# timer_power.net
KiCad netlist of a schematic drawn in Altium Designer
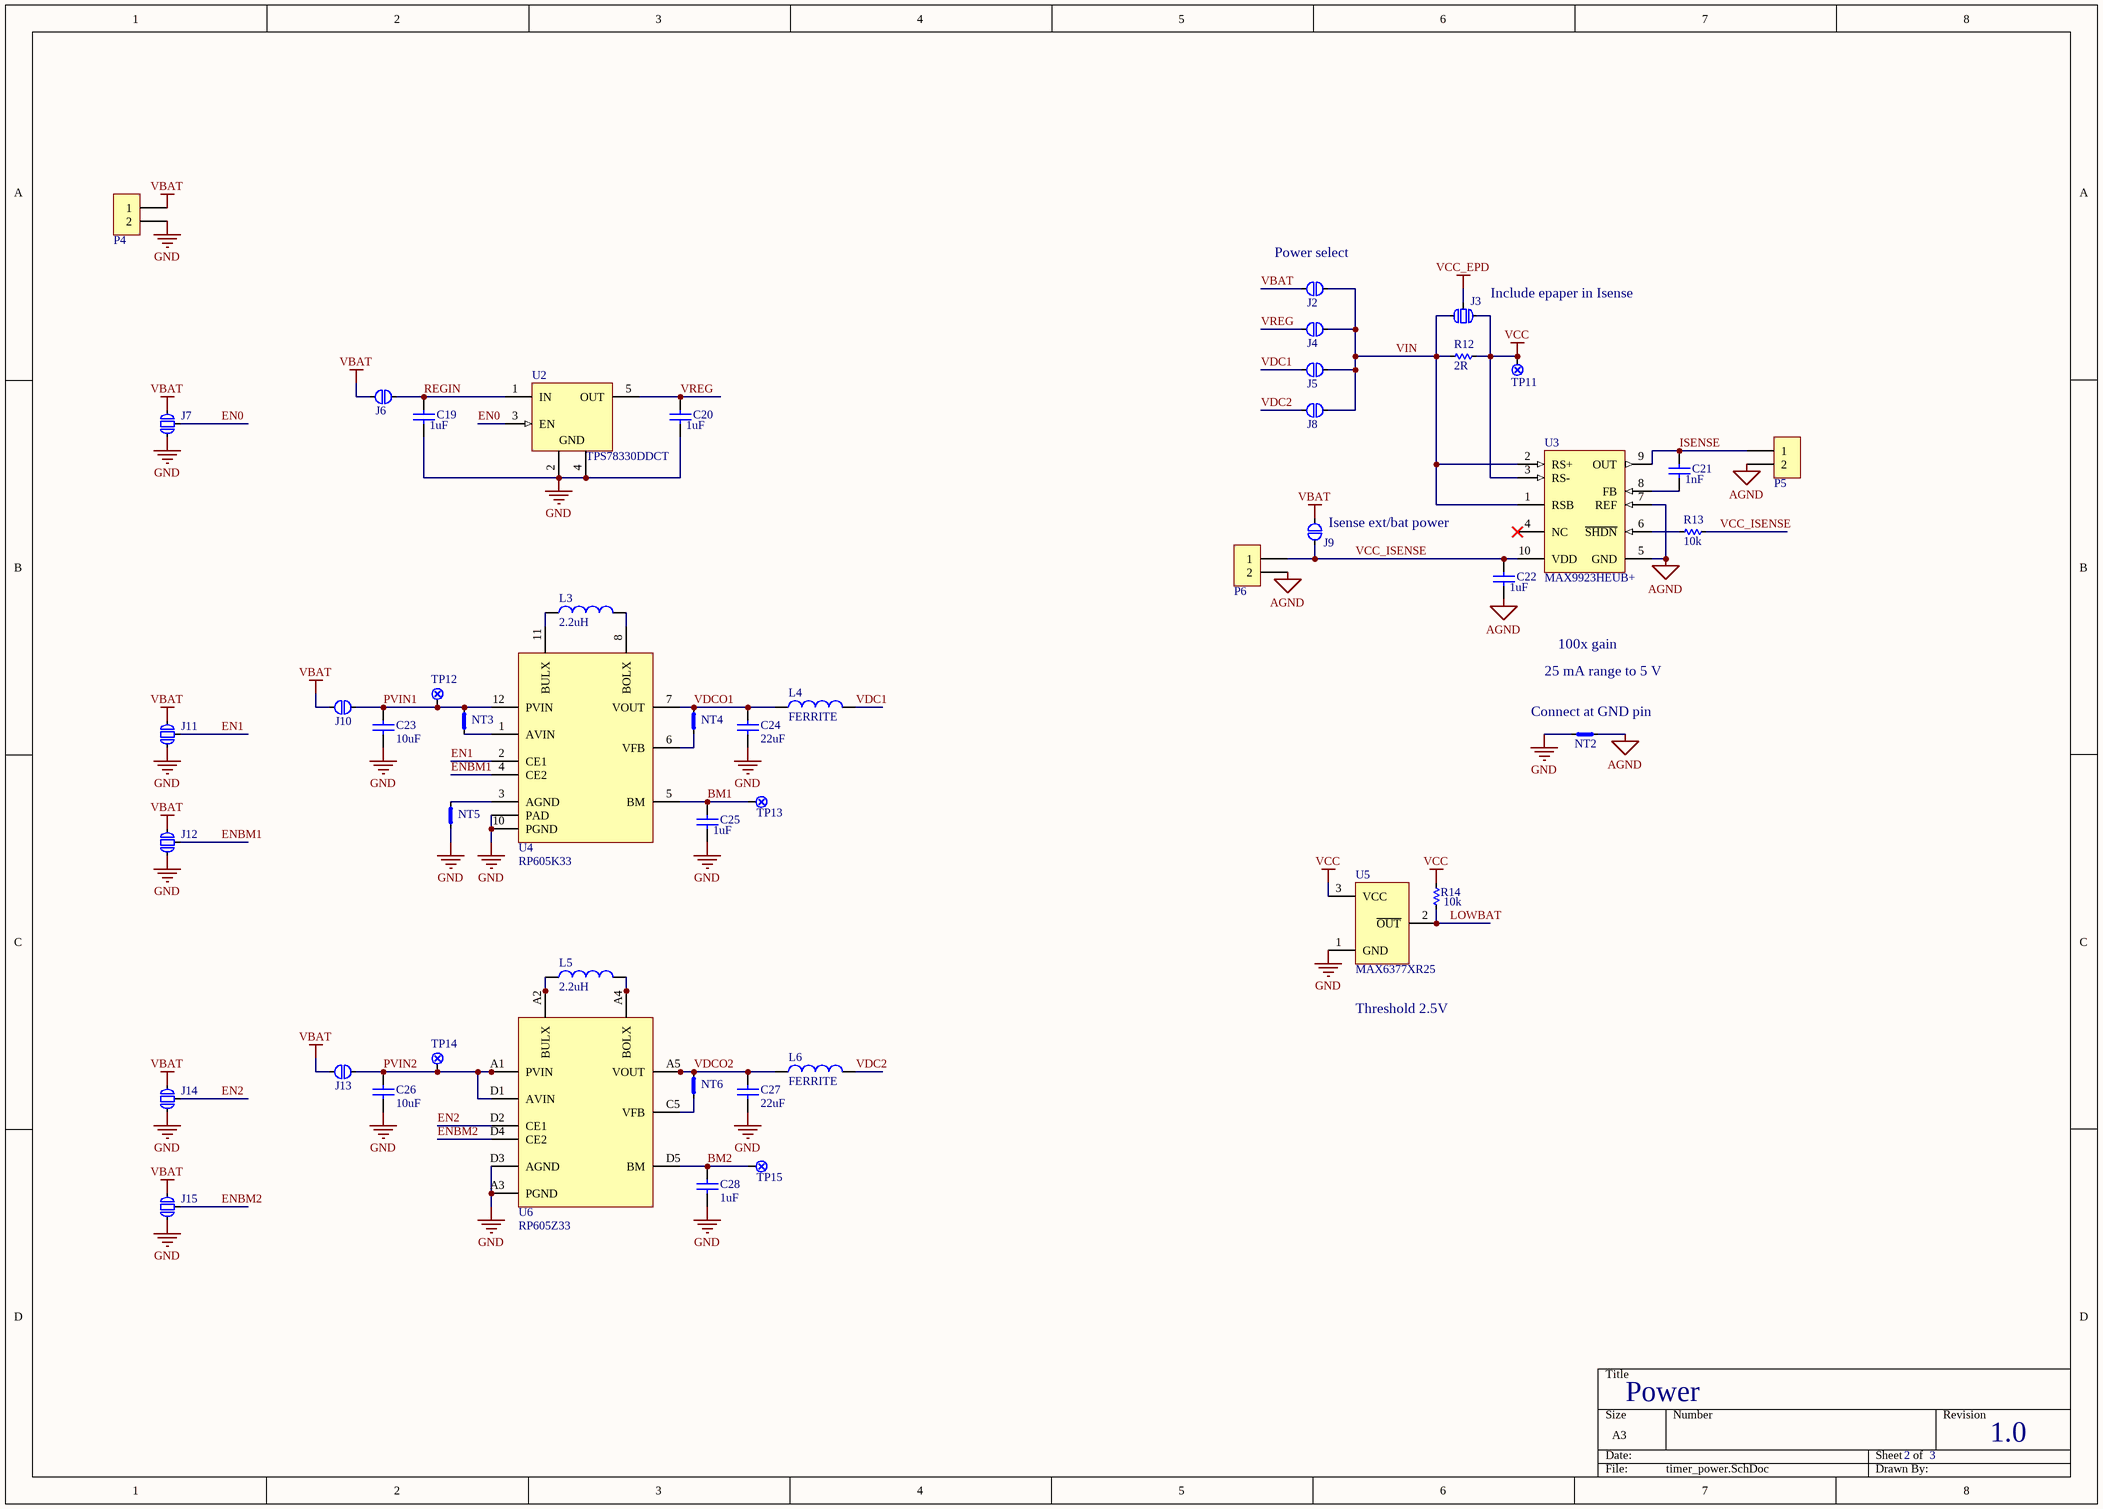
[diagram p0: timer_power.SchDoc]

(export (version "E")
  (design (tool "Eeschema 10.0.6"))
  (components
    (comp (ref "C19")
      (value "1uF")
      (footprint "C0603/1608")
      (description "Capacitor")
      (fields (field (name "TOLERANCE") "x%") (field (name "VOLTAGE") "6.3V"))
      (libsource (lib "ZMPlib") (part "CAP"))
    )
    (comp (ref "C20")
      (value "1uF")
      (footprint "C0603/1608")
      (description "Capacitor")
      (fields (field (name "TOLERANCE") "x%") (field (name "VOLTAGE") "6.3V"))
      (libsource (lib "ZMPlib") (part "CAP"))
    )
    (comp (ref "C21")
      (value "1nF")
      (footprint "C0603/1608")
      (description "Capacitor")
      (fields (field (name "TOLERANCE") "x%") (field (name "VOLTAGE") "6.3V"))
      (libsource (lib "ZMPlib") (part "CAP"))
    )
    (comp (ref "C22")
      (value "1uF")
      (footprint "C0603/1608")
      (description "Capacitor")
      (fields (field (name "TOLERANCE") "x%") (field (name "VOLTAGE") "6.3V"))
      (libsource (lib "ZMPlib") (part "CAP"))
    )
    (comp (ref "C23")
      (value "10uF")
      (footprint "C0805/2012")
      (description "Capacitor")
      (fields (field (name "TOLERANCE") "x%") (field (name "VOLTAGE") "6.3V"))
      (libsource (lib "ZMPlib") (part "CAP"))
    )
    (comp (ref "C24")
      (value "22uF")
      (footprint "C0805/2012")
      (description "Capacitor")
      (fields (field (name "TOLERANCE") "x%") (field (name "VOLTAGE") "6.3V"))
      (libsource (lib "ZMPlib") (part "CAP"))
    )
    (comp (ref "C25")
      (value "1uF")
      (footprint "C0603/1608")
      (description "Capacitor")
      (fields (field (name "TOLERANCE") "x%") (field (name "VOLTAGE") "6.3V"))
      (libsource (lib "ZMPlib") (part "CAP"))
    )
    (comp (ref "C26")
      (value "10uF")
      (footprint "C0805/2012")
      (description "Capacitor")
      (fields (field (name "TOLERANCE") "x%") (field (name "VOLTAGE") "6.3V"))
      (libsource (lib "ZMPlib") (part "CAP"))
    )
    (comp (ref "C27")
      (value "22uF")
      (footprint "C0805/2012")
      (description "Capacitor")
      (fields (field (name "TOLERANCE") "x%") (field (name "VOLTAGE") "6.3V"))
      (libsource (lib "ZMPlib") (part "CAP"))
    )
    (comp (ref "C28")
      (value "1uF")
      (footprint "C0603/1608")
      (description "Capacitor")
      (fields (field (name "TOLERANCE") "x%") (field (name "VOLTAGE") "6.3V"))
      (libsource (lib "ZMPlib") (part "CAP"))
    )
    (comp (ref "J2")
      (value "SEL2")
      (footprint "JMP2")
      (description "solderable jumper")
      (libsource (lib "ZMPlib") (part "SEL2"))
    )
    (comp (ref "J3")
      (value "SEL3")
      (footprint "JMP3")
      (description "solderable jumper")
      (libsource (lib "") (part "SEL3_1"))
    )
    (comp (ref "J4")
      (value "SEL2")
      (footprint "JMP2")
      (description "solderable jumper")
      (libsource (lib "ZMPlib") (part "SEL2"))
    )
    (comp (ref "J5")
      (value "SEL2")
      (footprint "JMP2")
      (description "solderable jumper")
      (libsource (lib "ZMPlib") (part "SEL2"))
    )
    (comp (ref "J6")
      (value "SEL2")
      (footprint "JMP2")
      (description "solderable jumper")
      (libsource (lib "ZMPlib") (part "SEL2"))
    )
    (comp (ref "J7")
      (value "SEL3")
      (footprint "JMP3")
      (description "solderable jumper")
      (libsource (lib "ZMPlib") (part "SEL3"))
    )
    (comp (ref "J8")
      (value "SEL2")
      (footprint "JMP2")
      (description "solderable jumper")
      (libsource (lib "ZMPlib") (part "SEL2"))
    )
    (comp (ref "J9")
      (value "SEL2")
      (footprint "JMP2")
      (description "solderable jumper")
      (libsource (lib "ZMPlib") (part "SEL2"))
    )
    (comp (ref "J10")
      (value "SEL2")
      (footprint "JMP2")
      (description "solderable jumper")
      (libsource (lib "ZMPlib") (part "SEL2"))
    )
    (comp (ref "J11")
      (value "SEL3")
      (footprint "JMP3")
      (description "solderable jumper")
      (libsource (lib "ZMPlib") (part "SEL3"))
    )
    (comp (ref "J12")
      (value "SEL3")
      (footprint "JMP3")
      (description "solderable jumper")
      (libsource (lib "ZMPlib") (part "SEL3"))
    )
    (comp (ref "J13")
      (value "SEL2")
      (footprint "JMP2")
      (description "solderable jumper")
      (libsource (lib "ZMPlib") (part "SEL2"))
    )
    (comp (ref "J14")
      (value "SEL3")
      (footprint "JMP3")
      (description "solderable jumper")
      (libsource (lib "ZMPlib") (part "SEL3"))
    )
    (comp (ref "J15")
      (value "SEL3")
      (footprint "JMP3")
      (description "solderable jumper")
      (libsource (lib "ZMPlib") (part "SEL3"))
    )
    (comp (ref "L3")
      (value "2.2uH")
      (footprint "IND3x3mm")
      (description "Inductor")
      (fields (field (name "Comment") "IND"))
      (libsource (lib "ZMPlib") (part "IND"))
    )
    (comp (ref "L4")
      (value "FERRITE")
      (footprint "R0603/1608")
      (description "Inductor")
      (fields (field (name "Comment") "IND"))
      (libsource (lib "ZMPlib") (part "IND"))
    )
    (comp (ref "L5")
      (value "2.2uH")
      (footprint "IND3x3mm")
      (description "Inductor")
      (fields (field (name "Comment") "IND"))
      (libsource (lib "ZMPlib") (part "IND"))
    )
    (comp (ref "L6")
      (value "FERRITE")
      (footprint "R0603/1608")
      (description "Inductor")
      (fields (field (name "Comment") "IND"))
      (libsource (lib "ZMPlib") (part "IND"))
    )
    (comp (ref "NT2")
      (value "NET_TIE")
      (footprint "NT2_0.5mm")
      (description "Link between nets")
      (libsource (lib "ZMPlib") (part "NET_TIE2"))
    )
    (comp (ref "NT3")
      (value "NET_TIE")
      (footprint "NT2_0.5mm")
      (description "Link between nets")
      (libsource (lib "ZMPlib") (part "NET_TIE2"))
    )
    (comp (ref "NT4")
      (value "NET_TIE")
      (footprint "NT2_0.5mm")
      (description "Link between nets")
      (libsource (lib "ZMPlib") (part "NET_TIE2"))
    )
    (comp (ref "NT5")
      (value "NET_TIE")
      (footprint "NT2_0.5mm")
      (description "Link between nets")
      (libsource (lib "ZMPlib") (part "NET_TIE2"))
    )
    (comp (ref "NT6")
      (value "NET_TIE")
      (footprint "NT2_0.5mm")
      (description "Link between nets")
      (libsource (lib "ZMPlib") (part "NET_TIE2"))
    )
    (comp (ref "P4")
      (value "SIL2")
      (footprint "PINS-2")
      (description "SIL package, 2 pins")
      (libsource (lib "ZMPlib") (part "SIL2"))
    )
    (comp (ref "P5")
      (value "SIL2")
      (footprint "PINS-2")
      (description "SIL package, 2 pins")
      (libsource (lib "") (part "SIL2_1"))
    )
    (comp (ref "P6")
      (value "SIL2")
      (footprint "PINS-2")
      (description "SIL package, 2 pins")
      (libsource (lib "ZMPlib") (part "SIL2"))
    )
    (comp (ref "R12")
      (value "2R")
      (footprint "R0805/2012")
      (description "Resistor")
      (fields (field (name "TOLERANCE") "x%") (field (name "Comment") "RES"))
      (libsource (lib "ZMPlib") (part "RES"))
    )
    (comp (ref "R13")
      (value "10k")
      (footprint "R0603/1608")
      (description "Resistor")
      (fields (field (name "TOLERANCE") "x%") (field (name "Comment") "RES"))
      (libsource (lib "ZMPlib") (part "RES"))
    )
    (comp (ref "R14")
      (value "10k")
      (footprint "R0603/1608")
      (description "Resistor")
      (fields (field (name "TOLERANCE") "x%") (field (name "Comment") "RES"))
      (libsource (lib "ZMPlib") (part "RES"))
    )
    (comp (ref "TP11")
      (value "TP")
      (footprint "TP-1.0")
      (description "Test point")
      (libsource (lib "ZMPlib") (part "TP"))
    )
    (comp (ref "TP12")
      (value "TP")
      (footprint "TP-1.0")
      (description "Test point")
      (libsource (lib "ZMPlib") (part "TP"))
    )
    (comp (ref "TP13")
      (value "TP")
      (footprint "TP-1.0")
      (description "Test point")
      (libsource (lib "ZMPlib") (part "TP"))
    )
    (comp (ref "TP14")
      (value "TP")
      (footprint "TP-1.0")
      (description "Test point")
      (libsource (lib "ZMPlib") (part "TP"))
    )
    (comp (ref "TP15")
      (value "TP")
      (footprint "TP-1.0")
      (description "Test point")
      (libsource (lib "ZMPlib") (part "TP"))
    )
    (comp (ref "U2")
      (value "TPS78330DDCT")
      (footprint "DDC0005A_L")
      (fields (field (name "MANUFACTURER") "Texas Instruments"))
      (libsource (lib "Altium Content Vault") (part "TI-TPS78XXX-DDC5"))
    )
    (comp (ref "U3")
      (value "MAX9923HEUB+")
      (footprint "MAXM-U10+2_N")
      (libsource (lib "Altium Content Vault") (part "MAX992X-U10+2"))
    )
    (comp (ref "U4")
      (value "RP605K33")
      (footprint "DFN(PLP)2730-12")
      (description "300mA Ultra-low Power Buck Boost DC/DC Converter with Battery Monitor, DFN-12 package")
      (libsource (lib "ZMPlib") (part "RP605xK"))
    )
    (comp (ref "U5")
      (value "MAX6377XR25")
      (footprint "SC70-3")
      (description "Ultra-Low-Power Voltage Detector")
      (libsource (lib "ZMPlib") (part "MAX637x"))
    )
    (comp (ref "U6")
      (value "RP605Z33")
      (footprint "WLCSP-20-P3")
      (description "300mA Ultra-low Power Buck Boost DC/DC Converter with Battery Monitor, WLCSP-20 package")
      (libsource (lib "ZMPlib") (part "RP605xZ"))
    )
  )
  (nets
    (net (code "1") (name "/BM1") (class "Default")
      (node (ref "C25") (pin "2") (pinfunction "2_2") (pintype "passive"))
      (node (ref "TP13") (pin "0") (pinfunction "0_0") (pintype "passive"))
      (node (ref "U4") (pin "5") (pinfunction "BM_5") (pintype "passive"))
    )
    (net (code "2") (name "/BM2") (class "Default")
      (node (ref "C28") (pin "2") (pinfunction "2_2") (pintype "passive"))
      (node (ref "TP15") (pin "0") (pinfunction "0_0") (pintype "passive"))
      (node (ref "U6") (pin "D5") (pinfunction "BM_D5") (pintype "passive"))
    )
    (net (code "3") (name "/EN0") (class "Default")
      (node (ref "J7") (pin "2") (pinfunction "2_2") (pintype "passive"))
      (node (ref "U2") (pin "3") (pinfunction "EN_3") (pintype "input"))
    )
    (net (code "4") (name "/EN1") (class "Default")
      (node (ref "J11") (pin "2") (pinfunction "2_2") (pintype "passive"))
      (node (ref "U4") (pin "2") (pinfunction "CE1_2") (pintype "passive"))
    )
    (net (code "5") (name "/EN2") (class "Default")
      (node (ref "J14") (pin "2") (pinfunction "2_2") (pintype "passive"))
      (node (ref "U6") (pin "D2") (pinfunction "CE1_D2") (pintype "passive"))
    )
    (net (code "6") (name "/ENBM1") (class "Default")
      (node (ref "J12") (pin "2") (pinfunction "2_2") (pintype "passive"))
      (node (ref "U4") (pin "4") (pinfunction "CE2_4") (pintype "passive"))
    )
    (net (code "7") (name "/ENBM2") (class "Default")
      (node (ref "J15") (pin "2") (pinfunction "2_2") (pintype "passive"))
      (node (ref "U6") (pin "D4") (pinfunction "CE2_D4") (pintype "passive"))
    )
    (net (code "8") (name "/ISENSE") (class "Default")
      (node (ref "C21") (pin "2") (pinfunction "2_2") (pintype "passive"))
      (node (ref "P5") (pin "1") (pinfunction "1_1") (pintype "passive"))
      (node (ref "U3") (pin "9") (pinfunction "OUT_9") (pintype "output"))
    )
    (net (code "9") (name "/LOWBAT") (class "Default")
      (node (ref "R14") (pin "2") (pinfunction "2_2") (pintype "passive"))
      (node (ref "U5") (pin "2") (pinfunction "~{OUT}_2") (pintype "open_collector"))
    )
    (net (code "10") (name "/PVIN1") (class "Default")
      (node (ref "C23") (pin "2") (pinfunction "2_2") (pintype "passive"))
      (node (ref "J10") (pin "2") (pinfunction "2_2") (pintype "passive"))
      (node (ref "NT3") (pin "2") (pinfunction "2_2") (pintype "passive"))
      (node (ref "TP12") (pin "0") (pinfunction "0_0") (pintype "passive"))
      (node (ref "U4") (pin "12") (pinfunction "PVIN_12") (pintype "power_in"))
    )
    (net (code "11") (name "/PVIN2") (class "Default")
      (node (ref "C26") (pin "2") (pinfunction "2_2") (pintype "passive"))
      (node (ref "J13") (pin "2") (pinfunction "2_2") (pintype "passive"))
      (node (ref "TP14") (pin "0") (pinfunction "0_0") (pintype "passive"))
      (node (ref "U6") (pin "A1") (pinfunction "PVIN_A1") (pintype "power_in"))
      (node (ref "U6") (pin "B1") (pinfunction "PVIN_B1") (pintype "power_in"))
      (node (ref "U6") (pin "C1") (pinfunction "PVIN_C1") (pintype "power_in"))
      (node (ref "U6") (pin "D1") (pinfunction "AVIN_D1") (pintype "power_in"))
    )
    (net (code "12") (name "/REGIN") (class "Default")
      (node (ref "C19") (pin "2") (pinfunction "2_2") (pintype "passive"))
      (node (ref "J6") (pin "2") (pinfunction "2_2") (pintype "passive"))
      (node (ref "U2") (pin "1") (pinfunction "IN_1") (pintype "power_in"))
    )
    (net (code "13") (name "/VCC_ISENSE") (class "Default")
      (node (ref "C22") (pin "2") (pinfunction "2_2") (pintype "passive"))
      (node (ref "J9") (pin "1") (pinfunction "1_1") (pintype "passive"))
      (node (ref "P6") (pin "1") (pinfunction "1_1") (pintype "passive"))
      (node (ref "R13") (pin "2") (pinfunction "2_2") (pintype "passive"))
      (node (ref "U3") (pin "10") (pinfunction "VDD_10") (pintype "power_in"))
    )
    (net (code "14") (name "/VDC1") (class "Default")
      (node (ref "J5") (pin "1") (pinfunction "1_1") (pintype "passive"))
      (node (ref "L4") (pin "2") (pinfunction "2_2") (pintype "passive"))
    )
    (net (code "15") (name "/VDC2") (class "Default")
      (node (ref "J8") (pin "1") (pinfunction "1_1") (pintype "passive"))
      (node (ref "L6") (pin "2") (pinfunction "2_2") (pintype "passive"))
    )
    (net (code "16") (name "/VDCO1") (class "Default")
      (node (ref "C24") (pin "2") (pinfunction "2_2") (pintype "passive"))
      (node (ref "L4") (pin "1") (pinfunction "1_1") (pintype "passive"))
      (node (ref "NT4") (pin "2") (pinfunction "2_2") (pintype "passive"))
      (node (ref "U4") (pin "7") (pinfunction "VOUT_7") (pintype "power_in"))
    )
    (net (code "17") (name "/VDCO2") (class "Default")
      (node (ref "C27") (pin "2") (pinfunction "2_2") (pintype "passive"))
      (node (ref "L6") (pin "1") (pinfunction "1_1") (pintype "passive"))
      (node (ref "NT6") (pin "2") (pinfunction "2_2") (pintype "passive"))
      (node (ref "U6") (pin "A5") (pinfunction "VOUT_A5") (pintype "power_in"))
      (node (ref "U6") (pin "B5") (pinfunction "VOUT_B5") (pintype "passive"))
    )
    (net (code "18") (name "/VIN") (class "Default")
      (node (ref "J2") (pin "2") (pinfunction "2_2") (pintype "passive"))
      (node (ref "J3") (pin "3") (pinfunction "3_3") (pintype "passive"))
      (node (ref "J4") (pin "2") (pinfunction "2_2") (pintype "passive"))
      (node (ref "J5") (pin "2") (pinfunction "2_2") (pintype "passive"))
      (node (ref "J8") (pin "2") (pinfunction "2_2") (pintype "passive"))
      (node (ref "R12") (pin "1") (pinfunction "1_1") (pintype "passive"))
      (node (ref "U3") (pin "1") (pinfunction "RSB_1") (pintype "power_in"))
      (node (ref "U3") (pin "2") (pinfunction "RS+_2") (pintype "input"))
    )
    (net (code "19") (name "/VREG") (class "Default")
      (node (ref "C20") (pin "2") (pinfunction "2_2") (pintype "passive"))
      (node (ref "J4") (pin "1") (pinfunction "1_1") (pintype "passive"))
      (node (ref "U2") (pin "5") (pinfunction "OUT_5") (pintype "power_in"))
    )
    (net (code "20") (name "AGND") (class "Default")
      (node (ref "C22") (pin "1") (pinfunction "1_1") (pintype "passive"))
      (node (ref "NT2") (pin "2") (pinfunction "2_2") (pintype "passive"))
      (node (ref "P5") (pin "2") (pinfunction "2_2") (pintype "passive"))
      (node (ref "P6") (pin "2") (pinfunction "2_2") (pintype "passive"))
      (node (ref "U3") (pin "5") (pinfunction "GND_5") (pintype "power_in"))
      (node (ref "U3") (pin "7") (pinfunction "REF_7") (pintype "input"))
    )
    (net (code "21") (name "GND") (class "Default")
      (node (ref "C19") (pin "1") (pinfunction "1_1") (pintype "passive"))
      (node (ref "C20") (pin "1") (pinfunction "1_1") (pintype "passive"))
      (node (ref "C23") (pin "1") (pinfunction "1_1") (pintype "passive"))
      (node (ref "C24") (pin "1") (pinfunction "1_1") (pintype "passive"))
      (node (ref "C25") (pin "1") (pinfunction "1_1") (pintype "passive"))
      (node (ref "C26") (pin "1") (pinfunction "1_1") (pintype "passive"))
      (node (ref "C27") (pin "1") (pinfunction "1_1") (pintype "passive"))
      (node (ref "C28") (pin "1") (pinfunction "1_1") (pintype "passive"))
      (node (ref "J11") (pin "1") (pinfunction "1_1") (pintype "passive"))
      (node (ref "J12") (pin "1") (pinfunction "1_1") (pintype "passive"))
      (node (ref "J14") (pin "1") (pinfunction "1_1") (pintype "passive"))
      (node (ref "J15") (pin "1") (pinfunction "1_1") (pintype "passive"))
      (node (ref "J7") (pin "1") (pinfunction "1_1") (pintype "passive"))
      (node (ref "NT2") (pin "1") (pinfunction "1_1") (pintype "passive"))
      (node (ref "NT5") (pin "1") (pinfunction "1_1") (pintype "passive"))
      (node (ref "P4") (pin "2") (pinfunction "2_2") (pintype "passive"))
      (node (ref "U2") (pin "2") (pinfunction "GND_2") (pintype "power_in"))
      (node (ref "U2") (pin "4") (pinfunction "GND_4") (pintype "power_in"))
      (node (ref "U4") (pin "0") (pinfunction "PAD_0") (pintype "passive"))
      (node (ref "U4") (pin "10") (pinfunction "PGND_10") (pintype "power_in"))
      (node (ref "U4") (pin "9") (pinfunction "PGND_9") (pintype "power_in"))
      (node (ref "U5") (pin "1") (pinfunction "GND_1") (pintype "power_in"))
      (node (ref "U6") (pin "A3") (pinfunction "PGND_A3") (pintype "power_in"))
      (node (ref "U6") (pin "B3") (pinfunction "PGND_B3") (pintype "power_in"))
      (node (ref "U6") (pin "C3") (pinfunction "PGND_C3") (pintype "power_in"))
      (node (ref "U6") (pin "D3") (pinfunction "AGND_D3") (pintype "power_in"))
    )
    (net (code "22") (name "Net-(L5-Pad1)") (class "Default")
      (node (ref "L5") (pin "1") (pinfunction "1_1") (pintype "passive"))
      (node (ref "U6") (pin "A2") (pinfunction "BULX_A2") (pintype "passive"))
      (node (ref "U6") (pin "B2") (pinfunction "BULX_B2") (pintype "passive"))
      (node (ref "U6") (pin "C2") (pinfunction "BULX_C2") (pintype "passive"))
    )
    (net (code "23") (name "Net-(L5-Pad2)") (class "Default")
      (node (ref "L5") (pin "2") (pinfunction "2_2") (pintype "passive"))
      (node (ref "U6") (pin "A4") (pinfunction "BOLX_A4") (pintype "passive"))
      (node (ref "U6") (pin "B4") (pinfunction "BOLX_B4") (pintype "passive"))
      (node (ref "U6") (pin "C4") (pinfunction "BOLX_C4") (pintype "passive"))
    )
    (net (code "24") (name "Net-(U3-FB)") (class "Default")
      (node (ref "C21") (pin "1") (pinfunction "1_1") (pintype "passive"))
      (node (ref "U3") (pin "8") (pinfunction "FB_8") (pintype "input"))
    )
    (net (code "25") (name "Net-(U3-~{SHDN})") (class "Default")
      (node (ref "R13") (pin "1") (pinfunction "1_1") (pintype "passive"))
      (node (ref "U3") (pin "6") (pinfunction "~{SHDN}_6") (pintype "input"))
    )
    (net (code "26") (name "Net-(U4-AGND)") (class "Default")
      (node (ref "NT5") (pin "2") (pinfunction "2_2") (pintype "passive"))
      (node (ref "U4") (pin "3") (pinfunction "AGND_3") (pintype "power_in"))
    )
    (net (code "27") (name "Net-(U4-AVIN)") (class "Default")
      (node (ref "NT3") (pin "1") (pinfunction "1_1") (pintype "passive"))
      (node (ref "U4") (pin "1") (pinfunction "AVIN_1") (pintype "power_in"))
    )
    (net (code "28") (name "Net-(U4-BOLX)") (class "Default")
      (node (ref "L3") (pin "2") (pinfunction "2_2") (pintype "passive"))
      (node (ref "U4") (pin "8") (pinfunction "BOLX_8") (pintype "passive"))
    )
    (net (code "29") (name "Net-(U4-BULX)") (class "Default")
      (node (ref "L3") (pin "1") (pinfunction "1_1") (pintype "passive"))
      (node (ref "U4") (pin "11") (pinfunction "BULX_11") (pintype "passive"))
    )
    (net (code "30") (name "Net-(U4-VFB)") (class "Default")
      (node (ref "NT4") (pin "1") (pinfunction "1_1") (pintype "passive"))
      (node (ref "U4") (pin "6") (pinfunction "VFB_6") (pintype "passive"))
    )
    (net (code "31") (name "Net-(U6-VFB)") (class "Default")
      (node (ref "NT6") (pin "1") (pinfunction "1_1") (pintype "passive"))
      (node (ref "U6") (pin "C5") (pinfunction "VFB_C5") (pintype "passive"))
    )
    (net (code "32") (name "VBAT") (class "Default")
      (node (ref "J10") (pin "1") (pinfunction "1_1") (pintype "passive"))
      (node (ref "J11") (pin "3") (pinfunction "3_3") (pintype "passive"))
      (node (ref "J12") (pin "3") (pinfunction "3_3") (pintype "passive"))
      (node (ref "J13") (pin "1") (pinfunction "1_1") (pintype "passive"))
      (node (ref "J14") (pin "3") (pinfunction "3_3") (pintype "passive"))
      (node (ref "J15") (pin "3") (pinfunction "3_3") (pintype "passive"))
      (node (ref "J2") (pin "1") (pinfunction "1_1") (pintype "passive"))
      (node (ref "J6") (pin "1") (pinfunction "1_1") (pintype "passive"))
      (node (ref "J7") (pin "3") (pinfunction "3_3") (pintype "passive"))
      (node (ref "J9") (pin "2") (pinfunction "2_2") (pintype "passive"))
      (node (ref "P4") (pin "1") (pinfunction "1_1") (pintype "passive"))
    )
    (net (code "33") (name "VCC") (class "Default")
      (node (ref "J3") (pin "1") (pinfunction "1_1") (pintype "passive"))
      (node (ref "R12") (pin "2") (pinfunction "2_2") (pintype "passive"))
      (node (ref "R14") (pin "1") (pinfunction "1_1") (pintype "passive"))
      (node (ref "TP11") (pin "0") (pinfunction "0_0") (pintype "passive"))
      (node (ref "U3") (pin "3") (pinfunction "RS-_3") (pintype "input"))
      (node (ref "U5") (pin "3") (pinfunction "VCC_3") (pintype "power_in"))
    )
    (net (code "34") (name "VCC_EPD") (class "Default")
      (node (ref "J3") (pin "2") (pinfunction "2_2") (pintype "passive"))
    )
    (net (code "35") (name "unconnected-(U3-NC-Pad4)") (class "Default")
      (node (ref "U3") (pin "4") (pinfunction "NC_4") (pintype "passive+no_connect"))
    )
  )
)
